# Serial_Controlled_Module.net
KiCad netlist of a schematic drawn in EAGLE
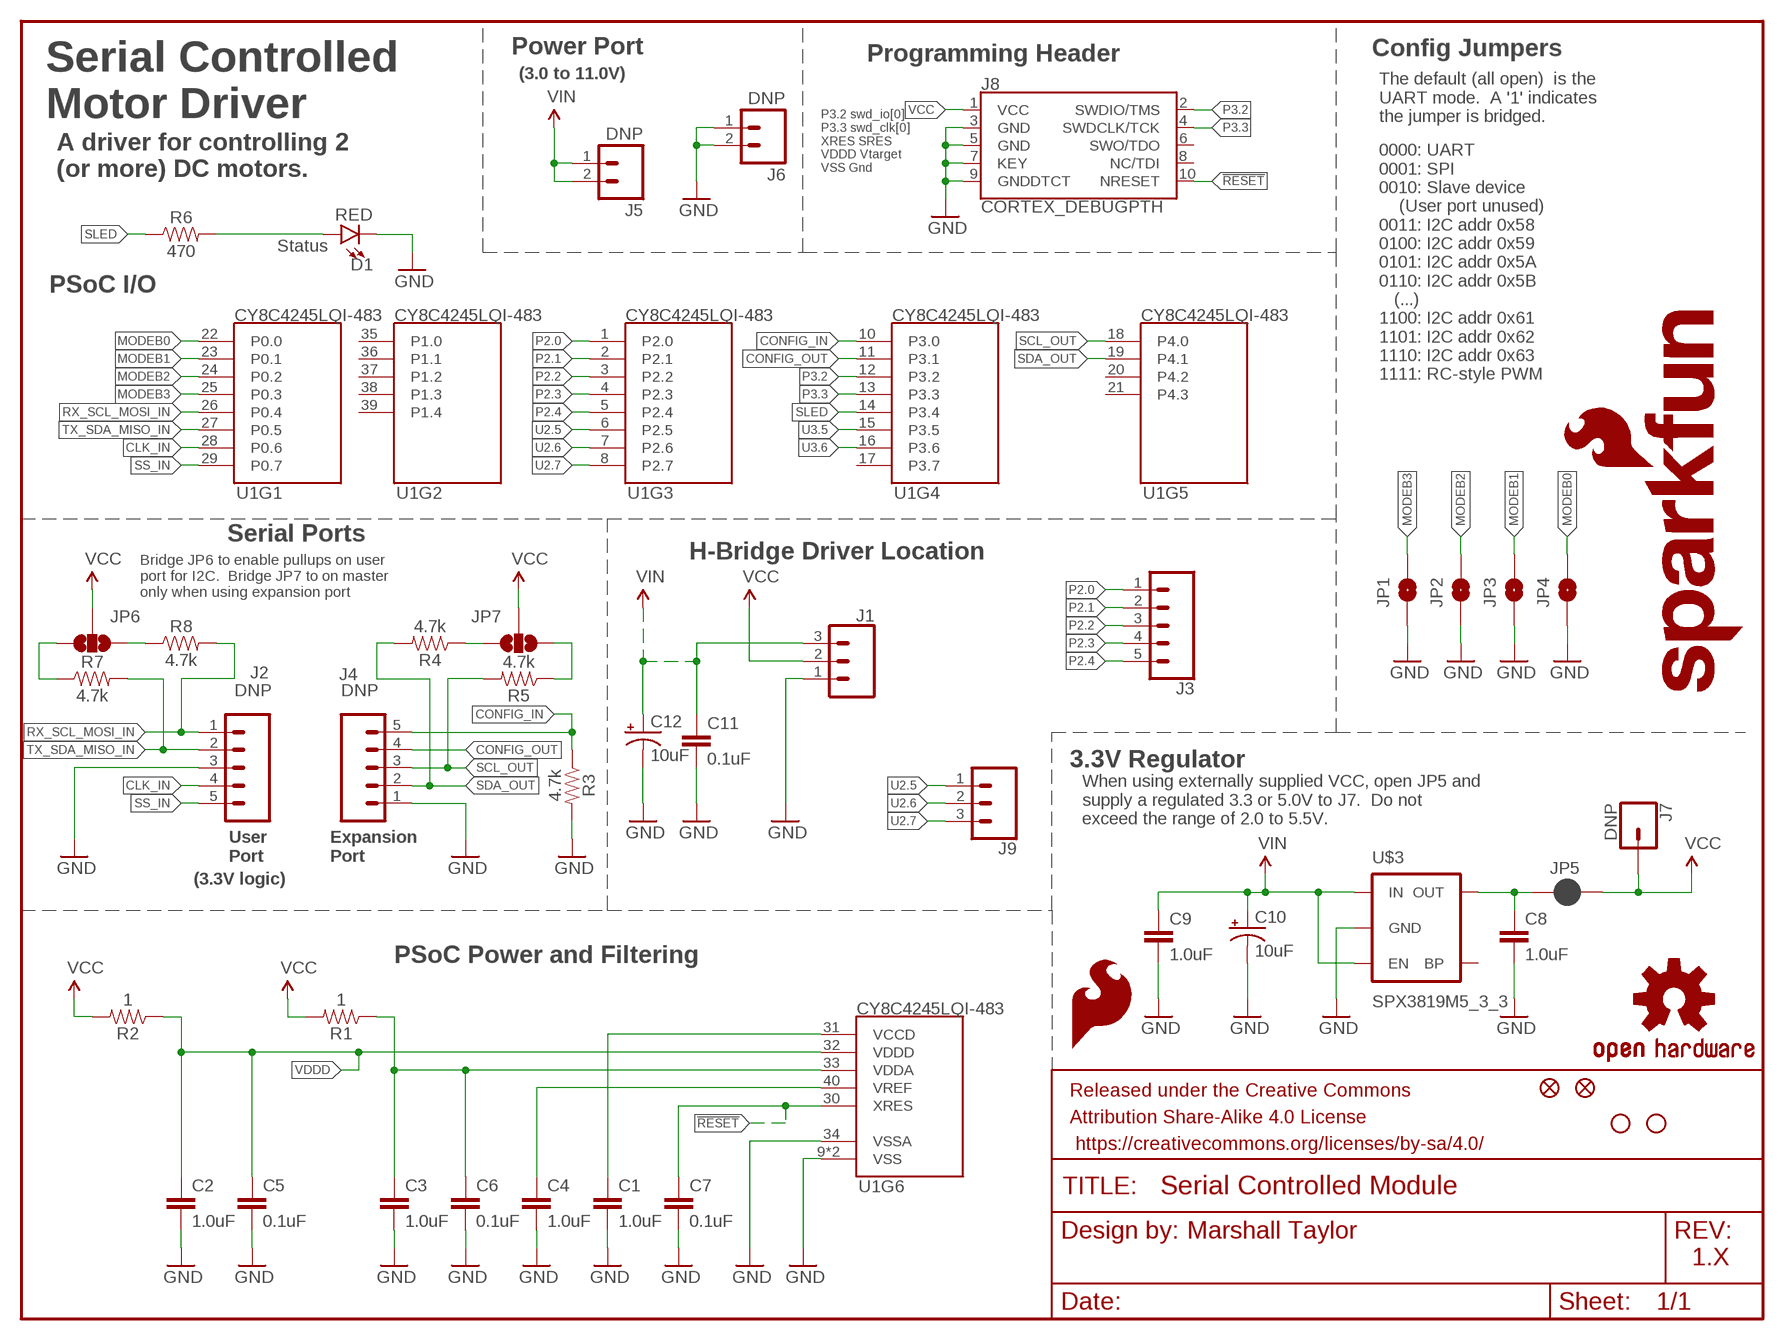
[diagram p0: schematic, sheet 1]

(export (version "E")
  (design (tool "Eeschema 10.0.6"))
  (components
    (comp (ref "C1")
      (value "1.0uF")
      (footprint "eagle-import:0402")
      (libsource (lib "eagle-import") (part "1.0UF-0402-16V-10%"))
    )
    (comp (ref "C2")
      (value "1.0uF")
      (footprint "eagle-import:0402")
      (libsource (lib "eagle-import") (part "1.0UF-0402-16V-10%"))
    )
    (comp (ref "C3")
      (value "1.0uF")
      (footprint "eagle-import:0402")
      (libsource (lib "eagle-import") (part "1.0UF-0402-16V-10%"))
    )
    (comp (ref "C4")
      (value "1.0uF")
      (footprint "eagle-import:0402")
      (libsource (lib "eagle-import") (part "1.0UF-0402-16V-10%"))
    )
    (comp (ref "C5")
      (value "0.1uF")
      (footprint "eagle-import:0402")
      (libsource (lib "eagle-import") (part "0.1UF-0402-16V-10%"))
    )
    (comp (ref "C6")
      (value "0.1uF")
      (footprint "eagle-import:0402")
      (libsource (lib "eagle-import") (part "0.1UF-0402-16V-10%"))
    )
    (comp (ref "C7")
      (value "0.1uF")
      (footprint "eagle-import:0402")
      (libsource (lib "eagle-import") (part "0.1UF-0402-16V-10%"))
    )
    (comp (ref "C8")
      (value "1.0uF")
      (footprint "eagle-import:0402")
      (libsource (lib "eagle-import") (part "1.0UF-0402-16V-10%"))
    )
    (comp (ref "C9")
      (value "1.0uF")
      (footprint "eagle-import:0402")
      (libsource (lib "eagle-import") (part "1.0UF-0402-16V-10%"))
    )
    (comp (ref "C10")
      (value "10uF")
      (footprint "eagle-import:EIA3216")
      (libsource (lib "eagle-import") (part "10UF-POLAR-EIA3216-16V-10%(TANT)"))
    )
    (comp (ref "C11")
      (value "0.1uF")
      (footprint "eagle-import:0402")
      (libsource (lib "eagle-import") (part "0.1UF-0402-16V-10%"))
    )
    (comp (ref "C12")
      (value "10uF")
      (footprint "eagle-import:EIA3216")
      (libsource (lib "eagle-import") (part "10UF-POLAR-EIA3216-16V-10%(TANT)"))
    )
    (comp (ref "D1")
      (value "RED")
      (footprint "eagle-import:LED-0603")
      (libsource (lib "eagle-import") (part "LED-RED0603"))
    )
    (comp (ref "FD1")
      (value "FIDUCIALUFIDUCIAL")
      (footprint "eagle-import:MICRO-FIDUCIAL")
      (libsource (lib "eagle-import") (part "FIDUCIALUFIDUCIAL"))
    )
    (comp (ref "FD2")
      (value "FIDUCIALUFIDUCIAL")
      (footprint "eagle-import:MICRO-FIDUCIAL")
      (libsource (lib "eagle-import") (part "FIDUCIALUFIDUCIAL"))
    )
    (comp (ref "FRAME1")
      (value "FRAME-LETTER")
      (footprint "eagle-import:CREATIVE_COMMONS")
      (libsource (lib "eagle-import") (part "FRAME-LETTER"))
    )
    (comp (ref "H3")
      (value "STAND-OFF")
      (footprint "eagle-import:STAND-OFF")
      (libsource (lib "eagle-import") (part "STAND-OFF"))
    )
    (comp (ref "H4")
      (value "STAND-OFF")
      (footprint "eagle-import:STAND-OFF")
      (libsource (lib "eagle-import") (part "STAND-OFF"))
    )
    (comp (ref "J1")
      (value "CONN_03PTH")
      (footprint "eagle-import:1X03")
      (libsource (lib "eagle-import") (part "CONN_03PTH"))
    )
    (comp (ref "J2")
      (value "DNP")
      (footprint "eagle-import:1X05@1")
      (libsource (lib "eagle-import") (part "M05PTH"))
    )
    (comp (ref "J3")
      (value "CONN_05PTH")
      (footprint "eagle-import:1X05")
      (libsource (lib "eagle-import") (part "CONN_05PTH"))
    )
    (comp (ref "J4")
      (value "DNP")
      (footprint "eagle-import:1X05@1")
      (libsource (lib "eagle-import") (part "M05PTH"))
    )
    (comp (ref "J5")
      (value "DNP")
      (footprint "eagle-import:1X02@1")
      (libsource (lib "eagle-import") (part "M02PTH"))
    )
    (comp (ref "J6")
      (value "DNP")
      (footprint "eagle-import:1X02@1")
      (libsource (lib "eagle-import") (part "M02PTH"))
    )
    (comp (ref "J7")
      (value "DNP")
      (footprint "eagle-import:1X01")
      (libsource (lib "eagle-import") (part "CONN_01PTH"))
    )
    (comp (ref "J8")
      (value "CORTEX_DEBUGPTH")
      (footprint "eagle-import:2X5-PTH-1.27MM")
      (libsource (lib "eagle-import") (part "CORTEX_DEBUGPTH"))
    )
    (comp (ref "J9")
      (value "CONN_03PTH")
      (footprint "eagle-import:1X03")
      (libsource (lib "eagle-import") (part "CONN_03PTH"))
    )
    (comp (ref "JP1")
      (value "JUMPER-PAD-2")
      (footprint "eagle-import:PAD-JUMPER-2-NO_YES_SILK")
      (libsource (lib "eagle-import") (part "JUMPER-PAD-2-NOYES_SILK"))
    )
    (comp (ref "JP2")
      (value "JUMPER-PAD-2")
      (footprint "eagle-import:PAD-JUMPER-2-NO_YES_SILK")
      (libsource (lib "eagle-import") (part "JUMPER-PAD-2-NOYES_SILK"))
    )
    (comp (ref "JP3")
      (value "JUMPER-PAD-2")
      (footprint "eagle-import:PAD-JUMPER-2-NO_YES_SILK")
      (libsource (lib "eagle-import") (part "JUMPER-PAD-2-NOYES_SILK"))
    )
    (comp (ref "JP4")
      (value "JUMPER-PAD-2")
      (footprint "eagle-import:PAD-JUMPER-2-NO_YES_SILK")
      (libsource (lib "eagle-import") (part "JUMPER-PAD-2-NOYES_SILK"))
    )
    (comp (ref "JP5")
      (value "JUMPER-PAD-2")
      (footprint "eagle-import:PAD-JUMPER-2-NC_BY_PASTE_YES_SILK")
      (libsource (lib "eagle-import") (part "JUMPER-PAD-2-NC_BY_PASTE"))
    )
    (comp (ref "JP6")
      (value "JUMPER-PAD-3-NOYES_SILK")
      (footprint "eagle-import:PAD-JUMPER-3-NO_YES_SILK")
      (libsource (lib "eagle-import") (part "JUMPER-PAD-3-NOYES_SILK"))
    )
    (comp (ref "JP7")
      (value "JUMPER-PAD-3-NOYES_SILK")
      (footprint "eagle-import:PAD-JUMPER-3-NO_YES_SILK")
      (libsource (lib "eagle-import") (part "JUMPER-PAD-3-NOYES_SILK"))
    )
    (comp (ref "LOGO1")
      (value "SFE_LOGO_FLAME.1_INCH")
      (footprint "eagle-import:SFE_LOGO_FLAME_.1")
      (libsource (lib "eagle-import") (part "SFE_LOGO_FLAME.1_INCH"))
    )
    (comp (ref "LOGO2")
      (value "OSHW-LOGOMINI")
      (footprint "eagle-import:OSHW-LOGO-MINI")
      (libsource (lib "eagle-import") (part "OSHW-LOGOMINI"))
    )
    (comp (ref "LOGO3")
      (value "SFE_LOGO_NAME_FLAME.1_INCH")
      (footprint "eagle-import:SFE_LOGO_NAME_FLAME_.1")
      (libsource (lib "eagle-import") (part "SFE_LOGO_NAME_FLAME.1_INCH"))
    )
    (comp (ref "R1")
      (value "1")
      (footprint "eagle-import:0603")
      (libsource (lib "eagle-import") (part "1OHM-0603-1/10W-1%"))
    )
    (comp (ref "R2")
      (value "1")
      (footprint "eagle-import:0603")
      (libsource (lib "eagle-import") (part "1OHM-0603-1/10W-1%"))
    )
    (comp (ref "R3")
      (value "4.7k")
      (footprint "eagle-import:0603")
      (libsource (lib "eagle-import") (part "4.7KOHM-0603-1/10W-1%"))
    )
    (comp (ref "R4")
      (value "4.7k")
      (footprint "eagle-import:0603")
      (libsource (lib "eagle-import") (part "4.7KOHM-0603-1/10W-1%"))
    )
    (comp (ref "R5")
      (value "4.7k")
      (footprint "eagle-import:0603")
      (libsource (lib "eagle-import") (part "4.7KOHM-0603-1/10W-1%"))
    )
    (comp (ref "R6")
      (value "470")
      (footprint "eagle-import:0603")
      (libsource (lib "eagle-import") (part "470OHM-0603-1/10W-1%"))
    )
    (comp (ref "R7")
      (value "4.7k")
      (footprint "eagle-import:0603")
      (libsource (lib "eagle-import") (part "4.7KOHM-0603-1/10W-1%"))
    )
    (comp (ref "R8")
      (value "4.7k")
      (footprint "eagle-import:0603")
      (libsource (lib "eagle-import") (part "4.7KOHM-0603-1/10W-1%"))
    )
    (comp (ref "U$3")
      (value "SPX3819M5_3_3")
      (footprint "eagle-import:SOT-23-5-VREG")
      (libsource (lib "eagle-import") (part "SPX3819"))
    )
    (comp (ref "U1")
      (value "CY8C4245LQI-483")
      (footprint "eagle-import:QFN-40")
      (libsource (lib "eagle-import") (part "CY8C4245LQI"))
    )
  )
  (nets
    (net (code "1") (name "/~{RESET}") (class "Default")
      (node (ref "C7") (pin "1") (pinfunction "1_1") (pintype "passive"))
      (node (ref "J8") (pin "10") (pinfunction "NRESET_10") (pintype "bidirectional"))
      (node (ref "U1") (pin "30") (pinfunction "XRES_30") (pintype "bidirectional"))
    )
    (net (code "2") (name "CLK_IN") (class "Default")
      (node (ref "J2") (pin "4") (pinfunction "4_4") (pintype "passive"))
      (node (ref "U1") (pin "28") (pinfunction "P0.6_28") (pintype "bidirectional"))
    )
    (net (code "3") (name "CONFIG_IN") (class "Default")
      (node (ref "J4") (pin "5") (pinfunction "5_5") (pintype "passive"))
      (node (ref "R3") (pin "1") (pinfunction "1_1") (pintype "passive"))
      (node (ref "U1") (pin "10") (pinfunction "P3.0_10") (pintype "bidirectional"))
    )
    (net (code "4") (name "CONFIG_OUT") (class "Default")
      (node (ref "J4") (pin "4") (pinfunction "4_4") (pintype "passive"))
      (node (ref "U1") (pin "11") (pinfunction "P3.1_11") (pintype "bidirectional"))
    )
    (net (code "5") (name "GND") (class "Default")
      (node (ref "C1") (pin "2") (pinfunction "2_2") (pintype "passive"))
      (node (ref "C10") (pin "-") (pinfunction "-_-") (pintype "passive"))
      (node (ref "C11") (pin "2") (pinfunction "2_2") (pintype "passive"))
      (node (ref "C12") (pin "-") (pinfunction "-_-") (pintype "passive"))
      (node (ref "C2") (pin "2") (pinfunction "2_2") (pintype "passive"))
      (node (ref "C3") (pin "2") (pinfunction "2_2") (pintype "passive"))
      (node (ref "C4") (pin "2") (pinfunction "2_2") (pintype "passive"))
      (node (ref "C5") (pin "2") (pinfunction "2_2") (pintype "passive"))
      (node (ref "C6") (pin "2") (pinfunction "2_2") (pintype "passive"))
      (node (ref "C7") (pin "2") (pinfunction "2_2") (pintype "passive"))
      (node (ref "C8") (pin "2") (pinfunction "2_2") (pintype "passive"))
      (node (ref "C9") (pin "2") (pinfunction "2_2") (pintype "passive"))
      (node (ref "D1") (pin "C") (pinfunction "C_C") (pintype "passive"))
      (node (ref "J1") (pin "1") (pinfunction "1_1") (pintype "passive"))
      (node (ref "J2") (pin "3") (pinfunction "3_3") (pintype "passive"))
      (node (ref "J4") (pin "1") (pinfunction "1_1") (pintype "passive"))
      (node (ref "J6") (pin "1") (pinfunction "1_1") (pintype "passive"))
      (node (ref "J6") (pin "2") (pinfunction "2_2") (pintype "passive"))
      (node (ref "J8") (pin "3") (pinfunction "GND_3") (pintype "bidirectional"))
      (node (ref "J8") (pin "5") (pinfunction "GND_5") (pintype "bidirectional"))
      (node (ref "J8") (pin "7") (pinfunction "KEY_7") (pintype "bidirectional"))
      (node (ref "J8") (pin "9") (pinfunction "GNDDTCT_9") (pintype "bidirectional"))
      (node (ref "JP1") (pin "1") (pinfunction "1_1") (pintype "passive"))
      (node (ref "JP2") (pin "1") (pinfunction "1_1") (pintype "passive"))
      (node (ref "JP3") (pin "1") (pinfunction "1_1") (pintype "passive"))
      (node (ref "JP4") (pin "1") (pinfunction "1_1") (pintype "passive"))
      (node (ref "R3") (pin "2") (pinfunction "2_2") (pintype "passive"))
      (node (ref "U$3") (pin "2") (pinfunction "GND_2") (pintype "input"))
      (node (ref "U1") (pin "34") (pinfunction "VSSA_34") (pintype "bidirectional"))
      (node (ref "U1") (pin "9") (pinfunction "VSS_9") (pintype "bidirectional"))
      (node (ref "U1") (pin "EP") (pinfunction "VSS_EP") (pintype "bidirectional"))
    )
    (net (code "6") (name "MODEB0") (class "Default")
      (node (ref "JP4") (pin "2") (pinfunction "2_2") (pintype "passive"))
      (node (ref "U1") (pin "22") (pinfunction "P0.0_22") (pintype "bidirectional"))
    )
    (net (code "7") (name "MODEB1") (class "Default")
      (node (ref "JP3") (pin "2") (pinfunction "2_2") (pintype "passive"))
      (node (ref "U1") (pin "23") (pinfunction "P0.1_23") (pintype "bidirectional"))
    )
    (net (code "8") (name "MODEB2") (class "Default")
      (node (ref "JP2") (pin "2") (pinfunction "2_2") (pintype "passive"))
      (node (ref "U1") (pin "24") (pinfunction "P0.2_24") (pintype "bidirectional"))
    )
    (net (code "9") (name "MODEB3") (class "Default")
      (node (ref "JP1") (pin "2") (pinfunction "2_2") (pintype "passive"))
      (node (ref "U1") (pin "25") (pinfunction "P0.3_25") (pintype "bidirectional"))
    )
    (net (code "10") (name "Net-(D1-PadA)") (class "Default")
      (node (ref "D1") (pin "A") (pinfunction "A_A") (pintype "passive"))
      (node (ref "R6") (pin "2") (pinfunction "2_2") (pintype "passive"))
    )
    (net (code "11") (name "Net-(JP6-Pad1)") (class "Default")
      (node (ref "JP6") (pin "1") (pinfunction "1_1") (pintype "passive"))
      (node (ref "R8") (pin "1") (pinfunction "1_1") (pintype "passive"))
    )
    (net (code "12") (name "Net-(JP6-Pad3)") (class "Default")
      (node (ref "JP6") (pin "3") (pinfunction "3_3") (pintype "passive"))
      (node (ref "R7") (pin "1") (pinfunction "1_1") (pintype "passive"))
    )
    (net (code "13") (name "Net-(JP7-Pad1)") (class "Default")
      (node (ref "JP7") (pin "1") (pinfunction "1_1") (pintype "passive"))
      (node (ref "R4") (pin "1") (pinfunction "1_1") (pintype "passive"))
    )
    (net (code "14") (name "Net-(JP7-Pad3)") (class "Default")
      (node (ref "JP7") (pin "3") (pinfunction "3_3") (pintype "passive"))
      (node (ref "R5") (pin "1") (pinfunction "1_1") (pintype "passive"))
    )
    (net (code "15") (name "Net-(U$3-OUT)") (class "Default")
      (node (ref "C8") (pin "1") (pinfunction "1_1") (pintype "passive"))
      (node (ref "JP5") (pin "1") (pinfunction "1_1") (pintype "passive"))
      (node (ref "U$3") (pin "5") (pinfunction "OUT_5") (pintype "passive"))
    )
    (net (code "16") (name "Net-(U1F-VCCD)") (class "Default")
      (node (ref "C1") (pin "1") (pinfunction "1_1") (pintype "passive"))
      (node (ref "U1") (pin "31") (pinfunction "VCCD_31") (pintype "bidirectional"))
    )
    (net (code "17") (name "Net-(U1F-VDDA)") (class "Default")
      (node (ref "C3") (pin "1") (pinfunction "1_1") (pintype "passive"))
      (node (ref "C6") (pin "1") (pinfunction "1_1") (pintype "passive"))
      (node (ref "R1") (pin "1") (pinfunction "1_1") (pintype "passive"))
      (node (ref "U1") (pin "33") (pinfunction "VDDA_33") (pintype "bidirectional"))
    )
    (net (code "18") (name "Net-(U1F-VREF)") (class "Default")
      (node (ref "C4") (pin "1") (pinfunction "1_1") (pintype "passive"))
      (node (ref "U1") (pin "40") (pinfunction "VREF_40") (pintype "bidirectional"))
    )
    (net (code "19") (name "P2.0") (class "Default")
      (node (ref "J3") (pin "1") (pinfunction "1_1") (pintype "passive"))
      (node (ref "U1") (pin "1") (pinfunction "P2.0_1") (pintype "bidirectional"))
    )
    (net (code "20") (name "P2.1") (class "Default")
      (node (ref "J3") (pin "2") (pinfunction "2_2") (pintype "passive"))
      (node (ref "U1") (pin "2") (pinfunction "P2.1_2") (pintype "bidirectional"))
    )
    (net (code "21") (name "P2.2") (class "Default")
      (node (ref "J3") (pin "3") (pinfunction "3_3") (pintype "passive"))
      (node (ref "U1") (pin "3") (pinfunction "P2.2_3") (pintype "bidirectional"))
    )
    (net (code "22") (name "P2.3") (class "Default")
      (node (ref "J3") (pin "4") (pinfunction "4_4") (pintype "passive"))
      (node (ref "U1") (pin "4") (pinfunction "P2.3_4") (pintype "bidirectional"))
    )
    (net (code "23") (name "P2.4") (class "Default")
      (node (ref "J3") (pin "5") (pinfunction "5_5") (pintype "passive"))
      (node (ref "U1") (pin "5") (pinfunction "P2.4_5") (pintype "bidirectional"))
    )
    (net (code "24") (name "P3.2") (class "Default")
      (node (ref "J8") (pin "2") (pinfunction "SWDIO/TMS_2") (pintype "bidirectional"))
      (node (ref "U1") (pin "12") (pinfunction "P3.2_12") (pintype "bidirectional"))
    )
    (net (code "25") (name "P3.3") (class "Default")
      (node (ref "J8") (pin "4") (pinfunction "SWDCLK/TCK_4") (pintype "bidirectional"))
      (node (ref "U1") (pin "13") (pinfunction "P3.3_13") (pintype "bidirectional"))
    )
    (net (code "26") (name "RX_SCL_MOSI_IN") (class "Default")
      (node (ref "J2") (pin "1") (pinfunction "1_1") (pintype "passive"))
      (node (ref "R8") (pin "2") (pinfunction "2_2") (pintype "passive"))
      (node (ref "U1") (pin "26") (pinfunction "P0.4_26") (pintype "bidirectional"))
    )
    (net (code "27") (name "SCL_OUT") (class "Default")
      (node (ref "J4") (pin "3") (pinfunction "3_3") (pintype "passive"))
      (node (ref "R5") (pin "2") (pinfunction "2_2") (pintype "passive"))
      (node (ref "U1") (pin "18") (pinfunction "P4.0_18") (pintype "bidirectional"))
    )
    (net (code "28") (name "SDA_OUT") (class "Default")
      (node (ref "J4") (pin "2") (pinfunction "2_2") (pintype "passive"))
      (node (ref "R4") (pin "2") (pinfunction "2_2") (pintype "passive"))
      (node (ref "U1") (pin "19") (pinfunction "P4.1_19") (pintype "bidirectional"))
    )
    (net (code "29") (name "SLED") (class "Default")
      (node (ref "R6") (pin "1") (pinfunction "1_1") (pintype "passive"))
      (node (ref "U1") (pin "14") (pinfunction "P3.4_14") (pintype "bidirectional"))
    )
    (net (code "30") (name "SS_IN") (class "Default")
      (node (ref "J2") (pin "5") (pinfunction "5_5") (pintype "passive"))
      (node (ref "U1") (pin "29") (pinfunction "P0.7_29") (pintype "bidirectional"))
    )
    (net (code "31") (name "TX_SDA_MISO_IN") (class "Default")
      (node (ref "J2") (pin "2") (pinfunction "2_2") (pintype "passive"))
      (node (ref "R7") (pin "2") (pinfunction "2_2") (pintype "passive"))
      (node (ref "U1") (pin "27") (pinfunction "P0.5_27") (pintype "bidirectional"))
    )
    (net (code "32") (name "U2.5") (class "Default")
      (node (ref "J9") (pin "1") (pinfunction "1_1") (pintype "passive"))
      (node (ref "U1") (pin "6") (pinfunction "P2.5_6") (pintype "bidirectional"))
    )
    (net (code "33") (name "U2.6") (class "Default")
      (node (ref "J9") (pin "2") (pinfunction "2_2") (pintype "passive"))
      (node (ref "U1") (pin "7") (pinfunction "P2.6_7") (pintype "bidirectional"))
    )
    (net (code "34") (name "U2.7") (class "Default")
      (node (ref "J9") (pin "3") (pinfunction "3_3") (pintype "passive"))
      (node (ref "U1") (pin "8") (pinfunction "P2.7_8") (pintype "bidirectional"))
    )
    (net (code "35") (name "U3.5") (class "Default")
      (node (ref "U1") (pin "15") (pinfunction "P3.5_15") (pintype "bidirectional"))
    )
    (net (code "36") (name "U3.6") (class "Default")
      (node (ref "U1") (pin "16") (pinfunction "P3.6_16") (pintype "bidirectional"))
    )
    (net (code "37") (name "VCC") (class "Default")
      (node (ref "J1") (pin "2") (pinfunction "2_2") (pintype "passive"))
      (node (ref "J7") (pin "1") (pinfunction "1_1") (pintype "passive"))
      (node (ref "J8") (pin "1") (pinfunction "VCC_1") (pintype "bidirectional"))
      (node (ref "JP5") (pin "2") (pinfunction "2_2") (pintype "passive"))
      (node (ref "JP6") (pin "2") (pinfunction "2_2") (pintype "passive"))
      (node (ref "JP7") (pin "2") (pinfunction "2_2") (pintype "passive"))
      (node (ref "R1") (pin "2") (pinfunction "2_2") (pintype "passive"))
      (node (ref "R2") (pin "2") (pinfunction "2_2") (pintype "passive"))
    )
    (net (code "38") (name "VDDD") (class "Default")
      (node (ref "C2") (pin "1") (pinfunction "1_1") (pintype "passive"))
      (node (ref "C5") (pin "1") (pinfunction "1_1") (pintype "passive"))
      (node (ref "R2") (pin "1") (pinfunction "1_1") (pintype "passive"))
      (node (ref "U1") (pin "32") (pinfunction "VDDD_32") (pintype "bidirectional"))
    )
    (net (code "39") (name "VIN") (class "Default")
      (node (ref "C10") (pin "+") (pinfunction "+_+") (pintype "passive"))
      (node (ref "C11") (pin "1") (pinfunction "1_1") (pintype "passive"))
      (node (ref "C12") (pin "+") (pinfunction "+_+") (pintype "passive"))
      (node (ref "C9") (pin "1") (pinfunction "1_1") (pintype "passive"))
      (node (ref "J1") (pin "3") (pinfunction "3_3") (pintype "passive"))
      (node (ref "J5") (pin "1") (pinfunction "1_1") (pintype "passive"))
      (node (ref "J5") (pin "2") (pinfunction "2_2") (pintype "passive"))
      (node (ref "U$3") (pin "1") (pinfunction "IN_1") (pintype "input"))
      (node (ref "U$3") (pin "3") (pinfunction "EN_3") (pintype "input"))
    )
    (net (code "40") (name "unconnected-(J8-NC{slash}TDI-Pad8)") (class "Default")
      (node (ref "J8") (pin "8") (pinfunction "NC/TDI_8") (pintype "bidirectional"))
    )
    (net (code "41") (name "unconnected-(J8-SWO{slash}TDO-Pad6)") (class "Default")
      (node (ref "J8") (pin "6") (pinfunction "SWO/TDO_6") (pintype "bidirectional"))
    )
    (net (code "42") (name "unconnected-(U$3-BP-Pad4)") (class "Default")
      (node (ref "U$3") (pin "4") (pinfunction "BP_4") (pintype "input"))
    )
    (net (code "43") (name "unconnected-(U1B-P1.0-Pad35)") (class "Default")
      (node (ref "U1") (pin "35") (pinfunction "P1.0_35") (pintype "bidirectional"))
    )
    (net (code "44") (name "unconnected-(U1B-P1.1-Pad36)") (class "Default")
      (node (ref "U1") (pin "36") (pinfunction "P1.1_36") (pintype "bidirectional"))
    )
    (net (code "45") (name "unconnected-(U1B-P1.2-Pad37)") (class "Default")
      (node (ref "U1") (pin "37") (pinfunction "P1.2_37") (pintype "bidirectional"))
    )
    (net (code "46") (name "unconnected-(U1B-P1.3-Pad38)") (class "Default")
      (node (ref "U1") (pin "38") (pinfunction "P1.3_38") (pintype "bidirectional"))
    )
    (net (code "47") (name "unconnected-(U1B-P1.4-Pad39)") (class "Default")
      (node (ref "U1") (pin "39") (pinfunction "P1.4_39") (pintype "bidirectional"))
    )
    (net (code "48") (name "unconnected-(U1D-P3.7-Pad17)") (class "Default")
      (node (ref "U1") (pin "17") (pinfunction "P3.7_17") (pintype "bidirectional"))
    )
    (net (code "49") (name "unconnected-(U1E-P4.2-Pad20)") (class "Default")
      (node (ref "U1") (pin "20") (pinfunction "P4.2_20") (pintype "bidirectional"))
    )
    (net (code "50") (name "unconnected-(U1E-P4.3-Pad21)") (class "Default")
      (node (ref "U1") (pin "21") (pinfunction "P4.3_21") (pintype "bidirectional"))
    )
  )
)
